# LPCB235_-_RS485_MUX_CONTROL.net
KiCad netlist of a schematic drawn in Altium Designer
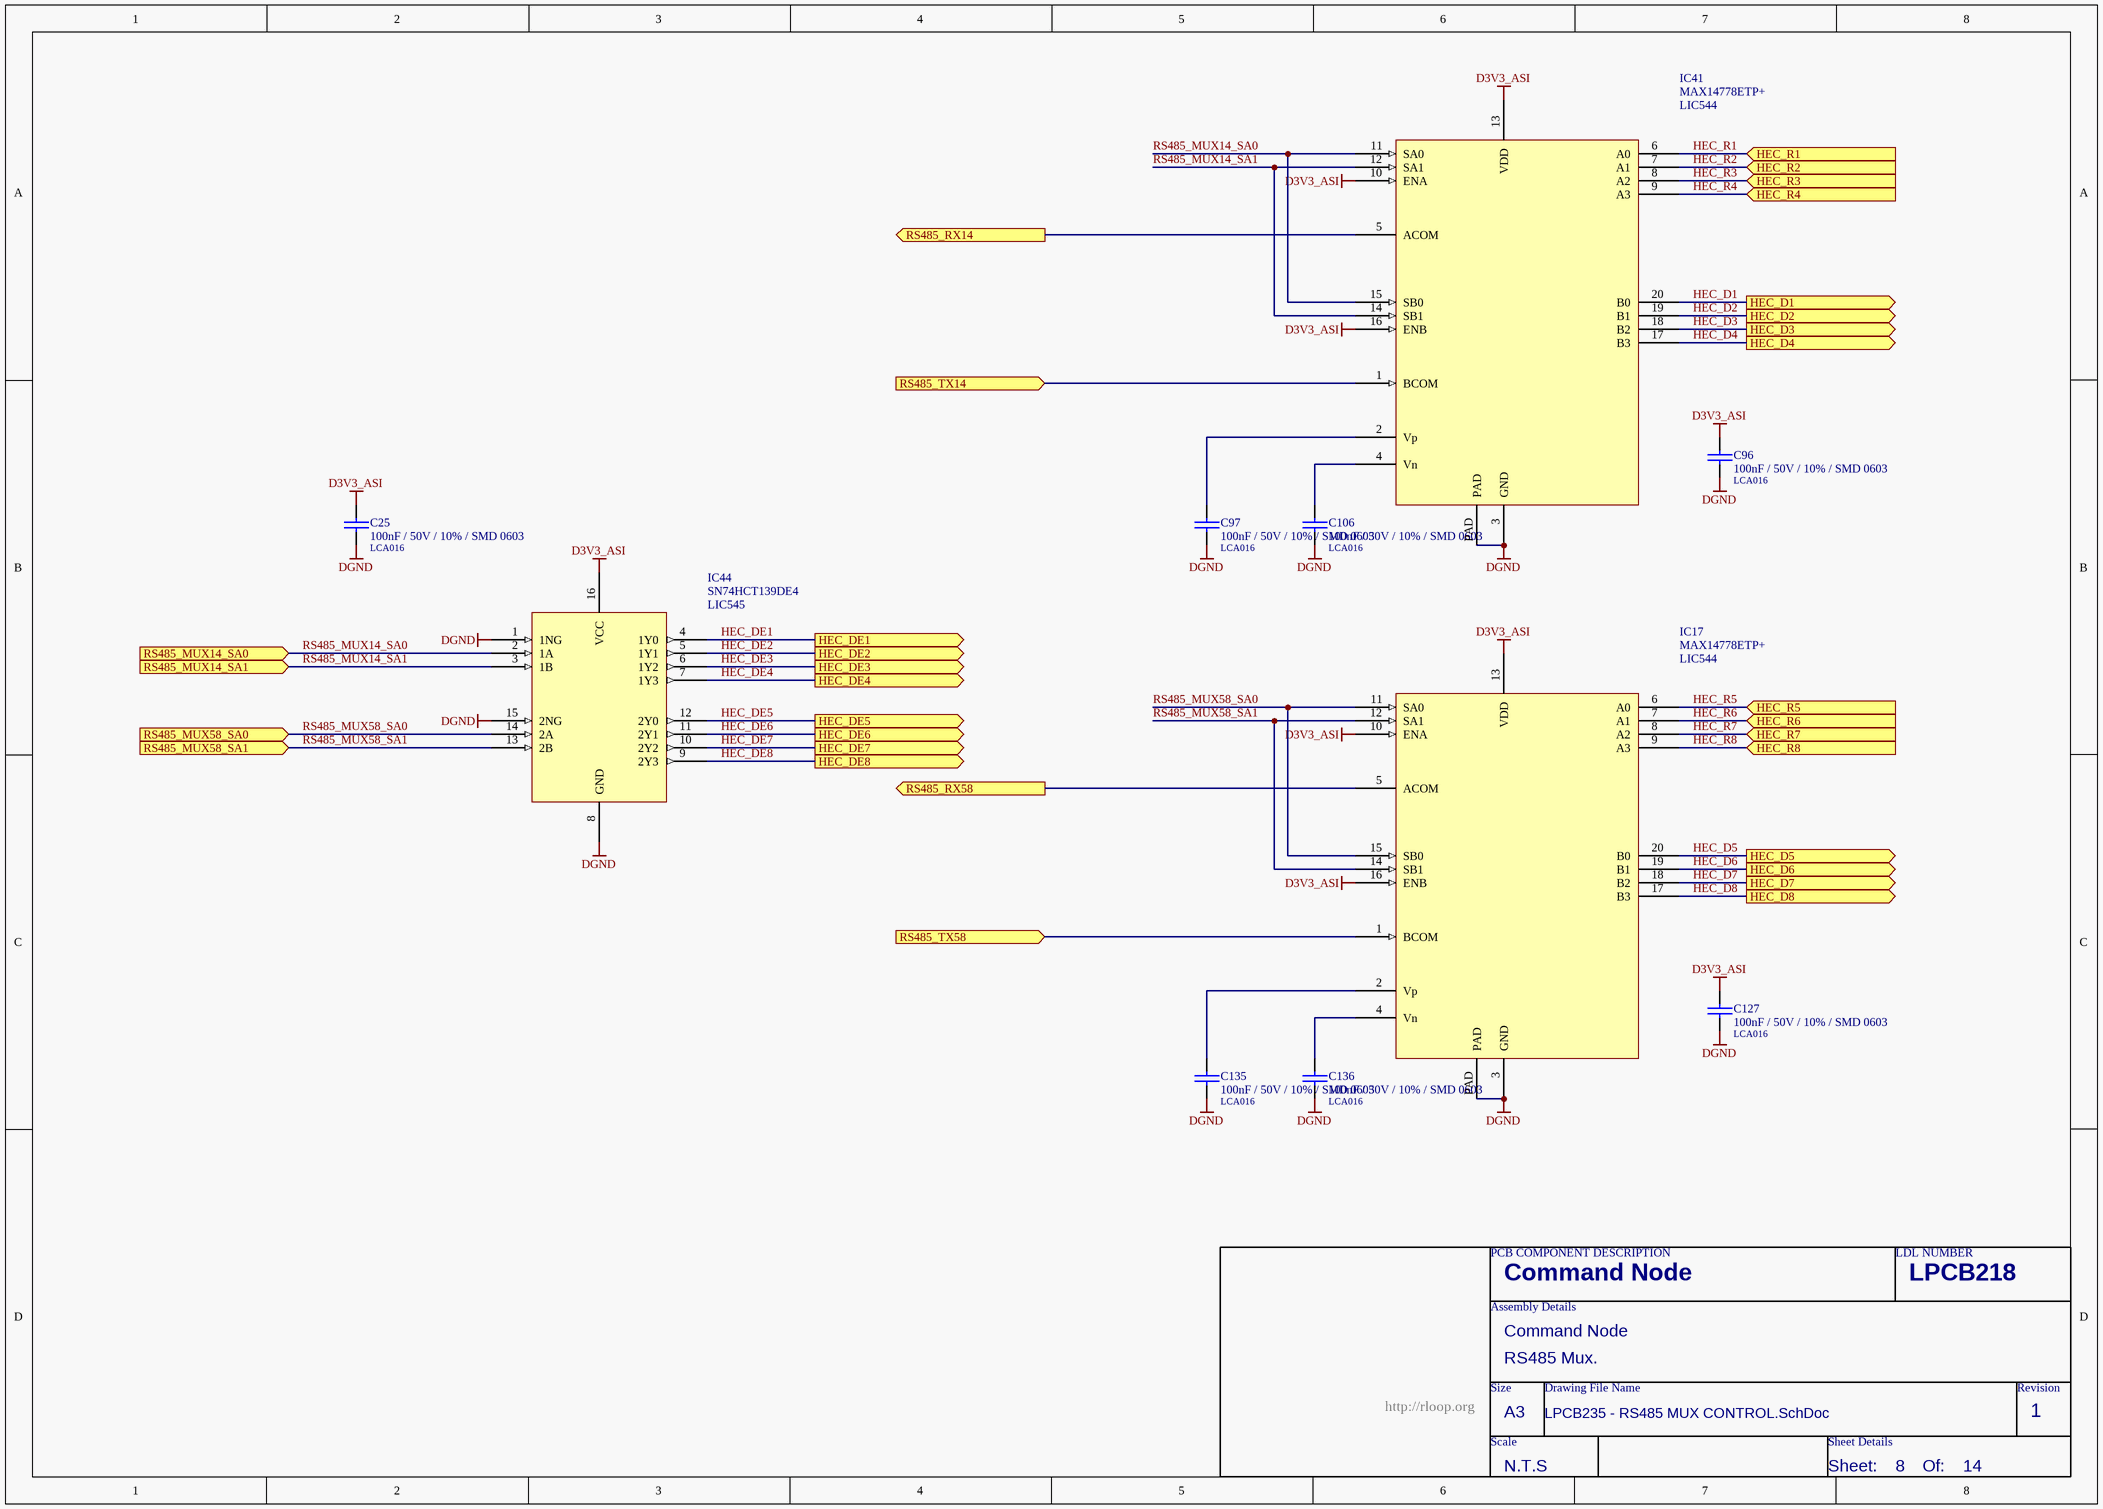
[diagram p0: LPCB235 - RS485 MUX CONTROL.SchDoc]

(export (version "E")
  (design (tool "Eeschema 10.0.6"))
  (components
    (comp (ref "C25")
      (value "100nF / 50V / 10% / SMD 0603")
      (footprint "LFP011__CC1608-0603-IPC7351_B")
      (description "Capacitor, Ceramic Chip, 100nF (0.1uF), 50V, 5%, SMD 0603 [LCA016]")
      (fields (field (name "LDL_NUMBER") "LCA016"))
      (libsource (lib "LDL_Capacitors") (part "100nF / 50V / 10% / SMD 0603"))
    )
    (comp (ref "C96")
      (value "100nF / 50V / 10% / SMD 0603")
      (footprint "LFP011__CC1608-0603-IPC7351_B")
      (description "Capacitor, Ceramic Chip, 100nF (0.1uF), 50V, 5%, SMD 0603 [LCA016]")
      (fields (field (name "LDL_NUMBER") "LCA016"))
      (libsource (lib "LDL_Capacitors") (part "100nF / 50V / 10% / SMD 0603"))
    )
    (comp (ref "C97")
      (value "100nF / 50V / 10% / SMD 0603")
      (footprint "LFP011__CC1608-0603-IPC7351_B")
      (description "Capacitor, Ceramic Chip, 100nF (0.1uF), 50V, 5%, SMD 0603 [LCA016]")
      (fields (field (name "LDL_NUMBER") "LCA016"))
      (libsource (lib "LDL_Capacitors") (part "100nF / 50V / 10% / SMD 0603"))
    )
    (comp (ref "C106")
      (value "100nF / 50V / 10% / SMD 0603")
      (footprint "LFP011__CC1608-0603-IPC7351_B")
      (description "Capacitor, Ceramic Chip, 100nF (0.1uF), 50V, 5%, SMD 0603 [LCA016]")
      (fields (field (name "LDL_NUMBER") "LCA016"))
      (libsource (lib "LDL_Capacitors") (part "100nF / 50V / 10% / SMD 0603"))
    )
    (comp (ref "C127")
      (value "100nF / 50V / 10% / SMD 0603")
      (footprint "LFP011__CC1608-0603-IPC7351_B")
      (description "Capacitor, Ceramic Chip, 100nF (0.1uF), 50V, 5%, SMD 0603 [LCA016]")
      (fields (field (name "LDL_NUMBER") "LCA016"))
      (libsource (lib "LDL_Capacitors") (part "100nF / 50V / 10% / SMD 0603"))
    )
    (comp (ref "C135")
      (value "100nF / 50V / 10% / SMD 0603")
      (footprint "LFP011__CC1608-0603-IPC7351_B")
      (description "Capacitor, Ceramic Chip, 100nF (0.1uF), 50V, 5%, SMD 0603 [LCA016]")
      (fields (field (name "LDL_NUMBER") "LCA016"))
      (libsource (lib "LDL_Capacitors") (part "100nF / 50V / 10% / SMD 0603"))
    )
    (comp (ref "C136")
      (value "100nF / 50V / 10% / SMD 0603")
      (footprint "LFP011__CC1608-0603-IPC7351_B")
      (description "Capacitor, Ceramic Chip, 100nF (0.1uF), 50V, 5%, SMD 0603 [LCA016]")
      (fields (field (name "LDL_NUMBER") "LCA016"))
      (libsource (lib "LDL_Capacitors") (part "100nF / 50V / 10% / SMD 0603"))
    )
    (comp (ref "IC17")
      (value "MAX14778ETP+")
      (footprint "LFP014__QFN65P500X500X80_HS-21N")
      (description "IC, Mux 25V, SMD QFN20 [LIC544]")
      (fields (field (name "LDL_NUMBER") "LIC544"))
      (libsource (lib "LDL_Semiconductors") (part "MAX14778ETP+"))
    )
    (comp (ref "IC41")
      (value "MAX14778ETP+")
      (footprint "LFP014__QFN65P500X500X80_HS-21N")
      (description "IC, Mux 25V, SMD QFN20 [LIC544]")
      (fields (field (name "LDL_NUMBER") "LIC544"))
      (libsource (lib "LDL_Semiconductors") (part "MAX14778ETP+"))
    )
    (comp (ref "IC44")
      (value "SN74HCT139DE4")
      (footprint "LFP079__SOP16")
      (description "IC, Dual 2-4 Demux, SMD SOIC-16")
      (fields (field (name "LDL_NUMBER") "LIC545"))
      (libsource (lib "LDL_Semiconductors") (part "SN74HCT139DE4"))
    )
  )
  (nets
    (net (code "1") (name "/HEC_D1") (class "Default")
      (node (ref "IC41") (pin "20") (pinfunction "B0_20") (pintype "passive"))
    )
    (net (code "2") (name "/HEC_D2") (class "Default")
      (node (ref "IC41") (pin "19") (pinfunction "B1_19") (pintype "passive"))
    )
    (net (code "3") (name "/HEC_D3") (class "Default")
      (node (ref "IC41") (pin "18") (pinfunction "B2_18") (pintype "passive"))
    )
    (net (code "4") (name "/HEC_D4") (class "Default")
      (node (ref "IC41") (pin "17") (pinfunction "B3_17") (pintype "passive"))
    )
    (net (code "5") (name "/HEC_D5") (class "Default")
      (node (ref "IC17") (pin "20") (pinfunction "B0_20") (pintype "passive"))
    )
    (net (code "6") (name "/HEC_D6") (class "Default")
      (node (ref "IC17") (pin "19") (pinfunction "B1_19") (pintype "passive"))
    )
    (net (code "7") (name "/HEC_D7") (class "Default")
      (node (ref "IC17") (pin "18") (pinfunction "B2_18") (pintype "passive"))
    )
    (net (code "8") (name "/HEC_D8") (class "Default")
      (node (ref "IC17") (pin "17") (pinfunction "B3_17") (pintype "passive"))
    )
    (net (code "9") (name "/HEC_DE1") (class "Default")
      (node (ref "IC44") (pin "4") (pinfunction "1Y0_4") (pintype "output"))
    )
    (net (code "10") (name "/HEC_DE2") (class "Default")
      (node (ref "IC44") (pin "5") (pinfunction "1Y1_5") (pintype "output"))
    )
    (net (code "11") (name "/HEC_DE3") (class "Default")
      (node (ref "IC44") (pin "6") (pinfunction "1Y2_6") (pintype "output"))
    )
    (net (code "12") (name "/HEC_DE4") (class "Default")
      (node (ref "IC44") (pin "7") (pinfunction "1Y3_7") (pintype "output"))
    )
    (net (code "13") (name "/HEC_DE5") (class "Default")
      (node (ref "IC44") (pin "12") (pinfunction "2Y0_12") (pintype "output"))
    )
    (net (code "14") (name "/HEC_DE6") (class "Default")
      (node (ref "IC44") (pin "11") (pinfunction "2Y1_11") (pintype "output"))
    )
    (net (code "15") (name "/HEC_DE7") (class "Default")
      (node (ref "IC44") (pin "10") (pinfunction "2Y2_10") (pintype "output"))
    )
    (net (code "16") (name "/HEC_DE8") (class "Default")
      (node (ref "IC44") (pin "9") (pinfunction "2Y3_9") (pintype "output"))
    )
    (net (code "17") (name "/HEC_R1") (class "Default")
      (node (ref "IC41") (pin "6") (pinfunction "A0_6") (pintype "passive"))
    )
    (net (code "18") (name "/HEC_R2") (class "Default")
      (node (ref "IC41") (pin "7") (pinfunction "A1_7") (pintype "passive"))
    )
    (net (code "19") (name "/HEC_R3") (class "Default")
      (node (ref "IC41") (pin "8") (pinfunction "A2_8") (pintype "passive"))
    )
    (net (code "20") (name "/HEC_R4") (class "Default")
      (node (ref "IC41") (pin "9") (pinfunction "A3_9") (pintype "passive"))
    )
    (net (code "21") (name "/HEC_R5") (class "Default")
      (node (ref "IC17") (pin "6") (pinfunction "A0_6") (pintype "passive"))
    )
    (net (code "22") (name "/HEC_R6") (class "Default")
      (node (ref "IC17") (pin "7") (pinfunction "A1_7") (pintype "passive"))
    )
    (net (code "23") (name "/HEC_R7") (class "Default")
      (node (ref "IC17") (pin "8") (pinfunction "A2_8") (pintype "passive"))
    )
    (net (code "24") (name "/HEC_R8") (class "Default")
      (node (ref "IC17") (pin "9") (pinfunction "A3_9") (pintype "passive"))
    )
    (net (code "25") (name "/RS485_MUX14_SA0") (class "Default")
      (node (ref "IC41") (pin "11") (pinfunction "SA0_11") (pintype "input"))
      (node (ref "IC41") (pin "15") (pinfunction "SB0_15") (pintype "input"))
      (node (ref "IC44") (pin "2") (pinfunction "1A_2") (pintype "input"))
    )
    (net (code "26") (name "/RS485_MUX14_SA1") (class "Default")
      (node (ref "IC41") (pin "12") (pinfunction "SA1_12") (pintype "input"))
      (node (ref "IC41") (pin "14") (pinfunction "SB1_14") (pintype "input"))
      (node (ref "IC44") (pin "3") (pinfunction "1B_3") (pintype "input"))
    )
    (net (code "27") (name "/RS485_MUX58_SA0") (class "Default")
      (node (ref "IC17") (pin "11") (pinfunction "SA0_11") (pintype "input"))
      (node (ref "IC17") (pin "15") (pinfunction "SB0_15") (pintype "input"))
      (node (ref "IC44") (pin "14") (pinfunction "2A_14") (pintype "input"))
    )
    (net (code "28") (name "/RS485_MUX58_SA1") (class "Default")
      (node (ref "IC17") (pin "12") (pinfunction "SA1_12") (pintype "input"))
      (node (ref "IC17") (pin "14") (pinfunction "SB1_14") (pintype "input"))
      (node (ref "IC44") (pin "13") (pinfunction "2B_13") (pintype "input"))
    )
    (net (code "29") (name "/RS485_RX14") (class "Default")
      (node (ref "IC41") (pin "5") (pinfunction "ACOM_5") (pintype "passive"))
    )
    (net (code "30") (name "/RS485_RX58") (class "Default")
      (node (ref "IC17") (pin "5") (pinfunction "ACOM_5") (pintype "passive"))
    )
    (net (code "31") (name "/RS485_TX14") (class "Default")
      (node (ref "IC41") (pin "1") (pinfunction "BCOM_1") (pintype "input"))
    )
    (net (code "32") (name "/RS485_TX58") (class "Default")
      (node (ref "IC17") (pin "1") (pinfunction "BCOM_1") (pintype "input"))
    )
    (net (code "33") (name "D3V3_ASI") (class "Default")
      (node (ref "C127") (pin "1") (pintype "passive"))
      (node (ref "C25") (pin "1") (pintype "passive"))
      (node (ref "C96") (pin "1") (pintype "passive"))
      (node (ref "IC17") (pin "10") (pinfunction "ENA_10") (pintype "input"))
      (node (ref "IC17") (pin "13") (pinfunction "VDD_13") (pintype "power_in"))
      (node (ref "IC17") (pin "16") (pinfunction "ENB_16") (pintype "input"))
      (node (ref "IC41") (pin "10") (pinfunction "ENA_10") (pintype "input"))
      (node (ref "IC41") (pin "13") (pinfunction "VDD_13") (pintype "power_in"))
      (node (ref "IC41") (pin "16") (pinfunction "ENB_16") (pintype "input"))
      (node (ref "IC44") (pin "16") (pinfunction "VCC_16") (pintype "power_in"))
    )
    (net (code "34") (name "DGND") (class "Default")
      (node (ref "C106") (pin "2") (pintype "passive"))
      (node (ref "C127") (pin "2") (pintype "passive"))
      (node (ref "C135") (pin "2") (pintype "passive"))
      (node (ref "C136") (pin "2") (pintype "passive"))
      (node (ref "C25") (pin "2") (pintype "passive"))
      (node (ref "C96") (pin "2") (pintype "passive"))
      (node (ref "C97") (pin "2") (pintype "passive"))
      (node (ref "IC17") (pin "3") (pinfunction "GND_3") (pintype "power_in"))
      (node (ref "IC17") (pin "PAD") (pinfunction "PAD_PAD") (pintype "power_in"))
      (node (ref "IC41") (pin "3") (pinfunction "GND_3") (pintype "power_in"))
      (node (ref "IC41") (pin "PAD") (pinfunction "PAD_PAD") (pintype "power_in"))
      (node (ref "IC44") (pin "1") (pinfunction "1NG_1") (pintype "input"))
      (node (ref "IC44") (pin "15") (pinfunction "2NG_15") (pintype "input"))
      (node (ref "IC44") (pin "8") (pinfunction "GND_8") (pintype "power_in"))
    )
    (net (code "35") (name "Net-(IC17-Vn)") (class "Default")
      (node (ref "C136") (pin "1") (pintype "passive"))
      (node (ref "IC17") (pin "4") (pinfunction "Vn_4") (pintype "passive"))
    )
    (net (code "36") (name "Net-(IC17-Vp)") (class "Default")
      (node (ref "C135") (pin "1") (pintype "passive"))
      (node (ref "IC17") (pin "2") (pinfunction "Vp_2") (pintype "passive"))
    )
    (net (code "37") (name "Net-(IC41-Vn)") (class "Default")
      (node (ref "C106") (pin "1") (pintype "passive"))
      (node (ref "IC41") (pin "4") (pinfunction "Vn_4") (pintype "passive"))
    )
    (net (code "38") (name "Net-(IC41-Vp)") (class "Default")
      (node (ref "C97") (pin "1") (pintype "passive"))
      (node (ref "IC41") (pin "2") (pinfunction "Vp_2") (pintype "passive"))
    )
  )
)
